# Relay_NPN.net
KiCad netlist of a schematic drawn in Altium Designer
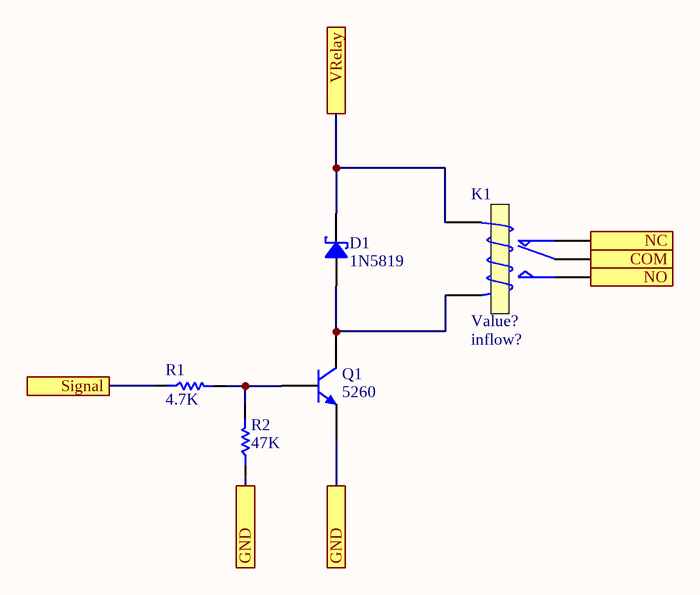
[diagram p0: Relay_NPN.SchDoc]

(export (version "E")
  (design (tool "Eeschema 10.0.6"))
  (components
    (comp (ref "D1")
      (value "1N5819")
      (footprint "430X270D")
      (description "Schottky Rectifiers")
      (fields (field (name "VALIDATION") "Valid"))
      (libsource (lib "aKaReZa") (part "Semi_Diod_Sch_1N5819_SMD"))
    )
    (comp (ref "K1")
      (value "Value?")
      (footprint "Relay 18.85x15.35x15.70")
      (description "SPDT Relay")
      (fields (field (name "INFLOW") "inflow?") (field (name "VALIDATION") "Valid"))
      (libsource (lib "aKaReZa") (part "SW_Relay_SPDT"))
    )
    (comp (ref "Q1")
      (value "NPN")
      (footprint "SOT23_N")
      (description "NPN Switching Transistors")
      (fields (field (name "INFLOW") "5260"))
      (libsource (lib "aKaReZa") (part "Semi_BJT_2N2222_SMD"))
    )
    (comp (ref "R1")
      (value "4.7K")
      (footprint "RES 0805 (2012X06L)")
      (description "Resistor")
      (fields (field (name "VALIDATION") "Valid"))
      (libsource (lib "aKaReZa") (part "Res_SMD_0805"))
    )
    (comp (ref "R2")
      (value "47K")
      (footprint "RES 0805 (2012X06L)")
      (description "Resistor")
      (fields (field (name "VALIDATION") "Valid"))
      (libsource (lib "aKaReZa") (part "Res_SMD_0805"))
    )
  )
  (nets
    (net (code "1") (name "/COM") (class "Default")
      (node (ref "K1") (pin "1") (pinfunction "COM_1") (pintype "passive"))
    )
    (net (code "2") (name "/GND") (class "Default")
      (node (ref "Q1") (pin "2") (pinfunction "E_2") (pintype "passive"))
      (node (ref "R2") (pin "1") (pinfunction "1_1") (pintype "passive"))
    )
    (net (code "3") (name "/NC") (class "Default")
      (node (ref "K1") (pin "2") (pinfunction "NC_2") (pintype "passive"))
    )
    (net (code "4") (name "/NO") (class "Default")
      (node (ref "K1") (pin "3") (pinfunction "NO_3") (pintype "passive"))
    )
    (net (code "5") (name "/Signal") (class "Default")
      (node (ref "R1") (pin "1") (pinfunction "1_1") (pintype "passive"))
    )
    (net (code "6") (name "/VRelay") (class "Default")
      (node (ref "D1") (pin "2") (pinfunction "2_2") (pintype "passive"))
      (node (ref "K1") (pin "4") (pinfunction "T1_4") (pintype "passive"))
    )
    (net (code "7") (name "Net-(K1-T2)") (class "Default")
      (node (ref "D1") (pin "1") (pinfunction "1_1") (pintype "passive"))
      (node (ref "K1") (pin "5") (pinfunction "T2_5") (pintype "passive"))
      (node (ref "Q1") (pin "3") (pinfunction "C_3") (pintype "passive"))
    )
    (net (code "8") (name "Net-(Q1-B)") (class "Default")
      (node (ref "Q1") (pin "1") (pinfunction "B_1") (pintype "passive"))
      (node (ref "R1") (pin "2") (pinfunction "2_2") (pintype "passive"))
      (node (ref "R2") (pin "2") (pinfunction "2_2") (pintype "passive"))
    )
  )
)
